# PCB_LED_CALENDAR__SINGLE_MONTH_31D.net
KiCad netlist of a schematic drawn in Altium Designer
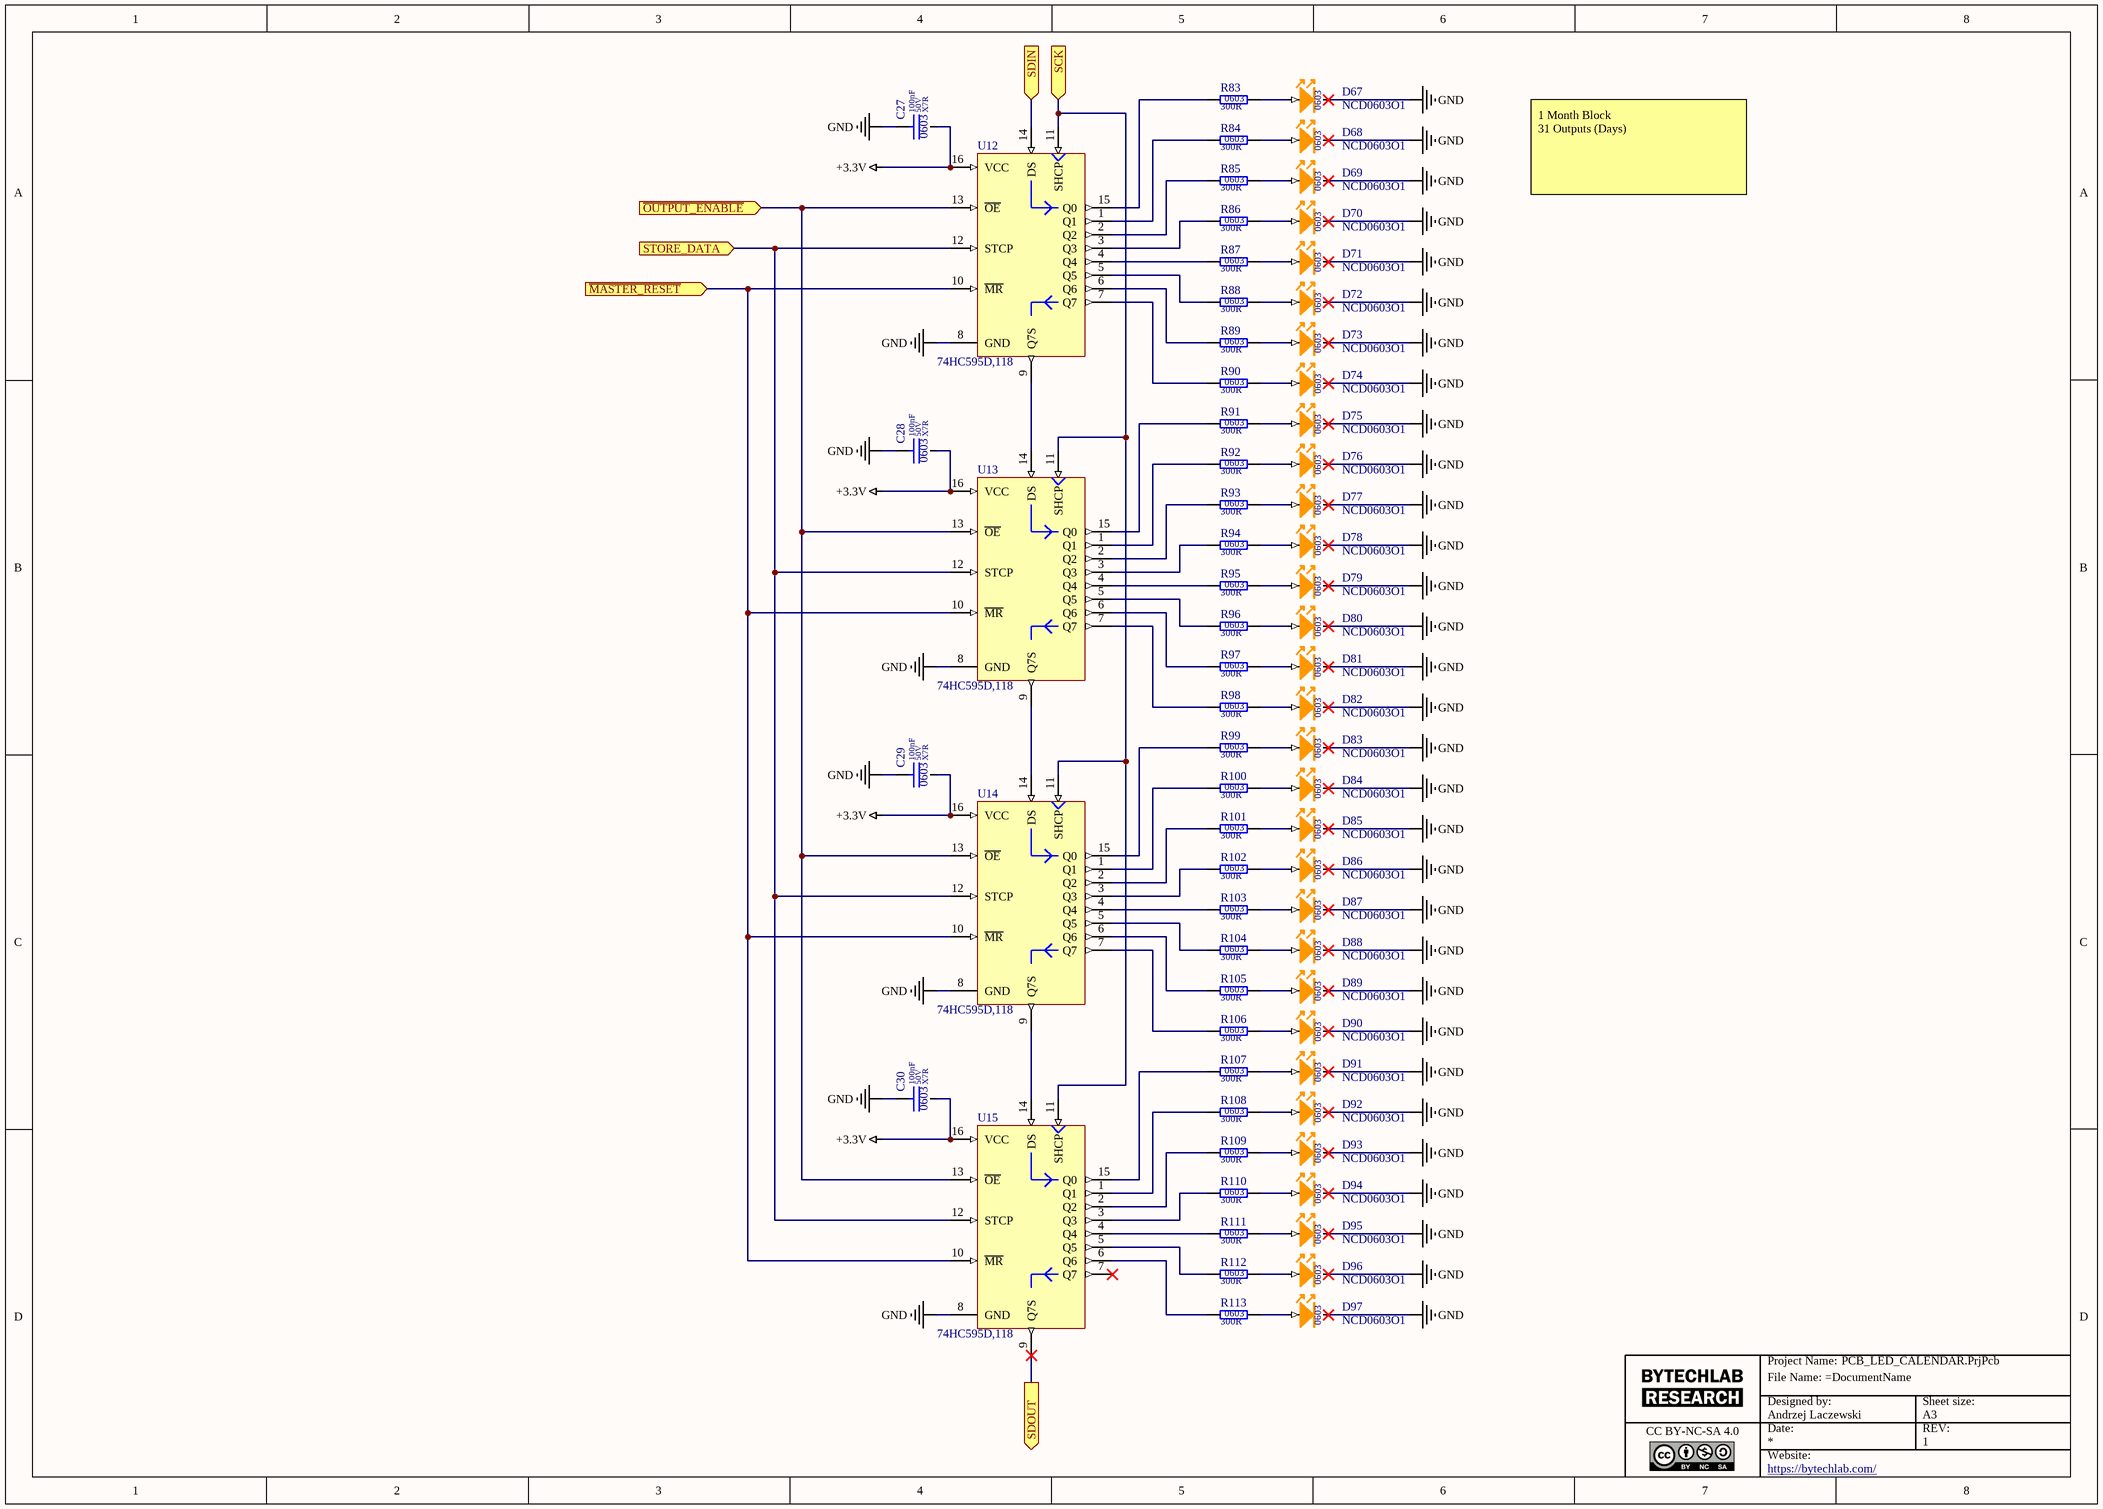
[diagram p0: PCB_LED_CALENDAR__SINGLE_MONTH_31D.SchDoc]

(export (version "E")
  (design (tool "Eeschema 10.0.6"))
  (components
    (comp (ref "C27")
      (value "100nF")
      (footprint "C_0603_1608")
      (description "Capacitor")
      (fields
        (field (name "DIELECTRIC") "X7R")
        (field (name "VOLTAGE") "50V")
        (field (name "SCH_FOOTPRINT") "0603")
        (field (name "PART NUMBER") "C_100nF_50V_X7R_0603_5")
        (field (name "MANUFACTURER") "Samsung")
      )
      (libsource (lib "Library") (part "C"))
    )
    (comp (ref "C28")
      (value "100nF")
      (footprint "C_0603_1608")
      (description "Capacitor")
      (fields
        (field (name "DIELECTRIC") "X7R")
        (field (name "VOLTAGE") "50V")
        (field (name "SCH_FOOTPRINT") "0603")
        (field (name "PART NUMBER") "C_100nF_50V_X7R_0603_5")
        (field (name "MANUFACTURER") "Samsung")
      )
      (libsource (lib "Library") (part "C"))
    )
    (comp (ref "C29")
      (value "100nF")
      (footprint "C_0603_1608")
      (description "Capacitor")
      (fields
        (field (name "DIELECTRIC") "X7R")
        (field (name "VOLTAGE") "50V")
        (field (name "SCH_FOOTPRINT") "0603")
        (field (name "PART NUMBER") "C_100nF_50V_X7R_0603_5")
        (field (name "MANUFACTURER") "Samsung")
      )
      (libsource (lib "Library") (part "C"))
    )
    (comp (ref "C30")
      (value "100nF")
      (footprint "C_0603_1608")
      (description "Capacitor")
      (fields
        (field (name "DIELECTRIC") "X7R")
        (field (name "VOLTAGE") "50V")
        (field (name "SCH_FOOTPRINT") "0603")
        (field (name "PART NUMBER") "C_100nF_50V_X7R_0603_5")
        (field (name "MANUFACTURER") "Samsung")
      )
      (libsource (lib "Library") (part "C"))
    )
    (comp (ref "D67")
      (value "NCD0603O1")
      (footprint "LED_0603")
      (description "Orange 130° 65mW 1.6V~2.6V 0603")
      (fields
        (field (name "MANUFACTURER") "Foshan NationStar Optoelectronics")
        (field (name "SCH_FOOTPRINT") "0603")
      )
      (libsource (lib "PCB_LED_CALENDAR") (part "OL_NCD0603O1"))
    )
    (comp (ref "D68")
      (value "NCD0603O1")
      (footprint "LED_0603")
      (description "Orange 130° 65mW 1.6V~2.6V 0603")
      (fields
        (field (name "MANUFACTURER") "Foshan NationStar Optoelectronics")
        (field (name "SCH_FOOTPRINT") "0603")
      )
      (libsource (lib "PCB_LED_CALENDAR") (part "OL_NCD0603O1"))
    )
    (comp (ref "D69")
      (value "NCD0603O1")
      (footprint "LED_0603")
      (description "Orange 130° 65mW 1.6V~2.6V 0603")
      (fields
        (field (name "MANUFACTURER") "Foshan NationStar Optoelectronics")
        (field (name "SCH_FOOTPRINT") "0603")
      )
      (libsource (lib "PCB_LED_CALENDAR") (part "OL_NCD0603O1"))
    )
    (comp (ref "D70")
      (value "NCD0603O1")
      (footprint "LED_0603")
      (description "Orange 130° 65mW 1.6V~2.6V 0603")
      (fields
        (field (name "MANUFACTURER") "Foshan NationStar Optoelectronics")
        (field (name "SCH_FOOTPRINT") "0603")
      )
      (libsource (lib "PCB_LED_CALENDAR") (part "OL_NCD0603O1"))
    )
    (comp (ref "D71")
      (value "NCD0603O1")
      (footprint "LED_0603")
      (description "Orange 130° 65mW 1.6V~2.6V 0603")
      (fields
        (field (name "MANUFACTURER") "Foshan NationStar Optoelectronics")
        (field (name "SCH_FOOTPRINT") "0603")
      )
      (libsource (lib "PCB_LED_CALENDAR") (part "OL_NCD0603O1"))
    )
    (comp (ref "D72")
      (value "NCD0603O1")
      (footprint "LED_0603")
      (description "Orange 130° 65mW 1.6V~2.6V 0603")
      (fields
        (field (name "MANUFACTURER") "Foshan NationStar Optoelectronics")
        (field (name "SCH_FOOTPRINT") "0603")
      )
      (libsource (lib "PCB_LED_CALENDAR") (part "OL_NCD0603O1"))
    )
    (comp (ref "D73")
      (value "NCD0603O1")
      (footprint "LED_0603")
      (description "Orange 130° 65mW 1.6V~2.6V 0603")
      (fields
        (field (name "MANUFACTURER") "Foshan NationStar Optoelectronics")
        (field (name "SCH_FOOTPRINT") "0603")
      )
      (libsource (lib "PCB_LED_CALENDAR") (part "OL_NCD0603O1"))
    )
    (comp (ref "D74")
      (value "NCD0603O1")
      (footprint "LED_0603")
      (description "Orange 130° 65mW 1.6V~2.6V 0603")
      (fields
        (field (name "MANUFACTURER") "Foshan NationStar Optoelectronics")
        (field (name "SCH_FOOTPRINT") "0603")
      )
      (libsource (lib "PCB_LED_CALENDAR") (part "OL_NCD0603O1"))
    )
    (comp (ref "D75")
      (value "NCD0603O1")
      (footprint "LED_0603")
      (description "Orange 130° 65mW 1.6V~2.6V 0603")
      (fields
        (field (name "MANUFACTURER") "Foshan NationStar Optoelectronics")
        (field (name "SCH_FOOTPRINT") "0603")
      )
      (libsource (lib "PCB_LED_CALENDAR") (part "OL_NCD0603O1"))
    )
    (comp (ref "D76")
      (value "NCD0603O1")
      (footprint "LED_0603")
      (description "Orange 130° 65mW 1.6V~2.6V 0603")
      (fields
        (field (name "MANUFACTURER") "Foshan NationStar Optoelectronics")
        (field (name "SCH_FOOTPRINT") "0603")
      )
      (libsource (lib "PCB_LED_CALENDAR") (part "OL_NCD0603O1"))
    )
    (comp (ref "D77")
      (value "NCD0603O1")
      (footprint "LED_0603")
      (description "Orange 130° 65mW 1.6V~2.6V 0603")
      (fields
        (field (name "MANUFACTURER") "Foshan NationStar Optoelectronics")
        (field (name "SCH_FOOTPRINT") "0603")
      )
      (libsource (lib "PCB_LED_CALENDAR") (part "OL_NCD0603O1"))
    )
    (comp (ref "D78")
      (value "NCD0603O1")
      (footprint "LED_0603")
      (description "Orange 130° 65mW 1.6V~2.6V 0603")
      (fields
        (field (name "MANUFACTURER") "Foshan NationStar Optoelectronics")
        (field (name "SCH_FOOTPRINT") "0603")
      )
      (libsource (lib "PCB_LED_CALENDAR") (part "OL_NCD0603O1"))
    )
    (comp (ref "D79")
      (value "NCD0603O1")
      (footprint "LED_0603")
      (description "Orange 130° 65mW 1.6V~2.6V 0603")
      (fields
        (field (name "MANUFACTURER") "Foshan NationStar Optoelectronics")
        (field (name "SCH_FOOTPRINT") "0603")
      )
      (libsource (lib "PCB_LED_CALENDAR") (part "OL_NCD0603O1"))
    )
    (comp (ref "D80")
      (value "NCD0603O1")
      (footprint "LED_0603")
      (description "Orange 130° 65mW 1.6V~2.6V 0603")
      (fields
        (field (name "MANUFACTURER") "Foshan NationStar Optoelectronics")
        (field (name "SCH_FOOTPRINT") "0603")
      )
      (libsource (lib "PCB_LED_CALENDAR") (part "OL_NCD0603O1"))
    )
    (comp (ref "D81")
      (value "NCD0603O1")
      (footprint "LED_0603")
      (description "Orange 130° 65mW 1.6V~2.6V 0603")
      (fields
        (field (name "MANUFACTURER") "Foshan NationStar Optoelectronics")
        (field (name "SCH_FOOTPRINT") "0603")
      )
      (libsource (lib "PCB_LED_CALENDAR") (part "OL_NCD0603O1"))
    )
    (comp (ref "D82")
      (value "NCD0603O1")
      (footprint "LED_0603")
      (description "Orange 130° 65mW 1.6V~2.6V 0603")
      (fields
        (field (name "MANUFACTURER") "Foshan NationStar Optoelectronics")
        (field (name "SCH_FOOTPRINT") "0603")
      )
      (libsource (lib "PCB_LED_CALENDAR") (part "OL_NCD0603O1"))
    )
    (comp (ref "D83")
      (value "NCD0603O1")
      (footprint "LED_0603")
      (description "Orange 130° 65mW 1.6V~2.6V 0603")
      (fields
        (field (name "MANUFACTURER") "Foshan NationStar Optoelectronics")
        (field (name "SCH_FOOTPRINT") "0603")
      )
      (libsource (lib "PCB_LED_CALENDAR") (part "OL_NCD0603O1"))
    )
    (comp (ref "D84")
      (value "NCD0603O1")
      (footprint "LED_0603")
      (description "Orange 130° 65mW 1.6V~2.6V 0603")
      (fields
        (field (name "MANUFACTURER") "Foshan NationStar Optoelectronics")
        (field (name "SCH_FOOTPRINT") "0603")
      )
      (libsource (lib "PCB_LED_CALENDAR") (part "OL_NCD0603O1"))
    )
    (comp (ref "D85")
      (value "NCD0603O1")
      (footprint "LED_0603")
      (description "Orange 130° 65mW 1.6V~2.6V 0603")
      (fields
        (field (name "MANUFACTURER") "Foshan NationStar Optoelectronics")
        (field (name "SCH_FOOTPRINT") "0603")
      )
      (libsource (lib "PCB_LED_CALENDAR") (part "OL_NCD0603O1"))
    )
    (comp (ref "D86")
      (value "NCD0603O1")
      (footprint "LED_0603")
      (description "Orange 130° 65mW 1.6V~2.6V 0603")
      (fields
        (field (name "MANUFACTURER") "Foshan NationStar Optoelectronics")
        (field (name "SCH_FOOTPRINT") "0603")
      )
      (libsource (lib "PCB_LED_CALENDAR") (part "OL_NCD0603O1"))
    )
    (comp (ref "D87")
      (value "NCD0603O1")
      (footprint "LED_0603")
      (description "Orange 130° 65mW 1.6V~2.6V 0603")
      (fields
        (field (name "MANUFACTURER") "Foshan NationStar Optoelectronics")
        (field (name "SCH_FOOTPRINT") "0603")
      )
      (libsource (lib "PCB_LED_CALENDAR") (part "OL_NCD0603O1"))
    )
    (comp (ref "D88")
      (value "NCD0603O1")
      (footprint "LED_0603")
      (description "Orange 130° 65mW 1.6V~2.6V 0603")
      (fields
        (field (name "MANUFACTURER") "Foshan NationStar Optoelectronics")
        (field (name "SCH_FOOTPRINT") "0603")
      )
      (libsource (lib "PCB_LED_CALENDAR") (part "OL_NCD0603O1"))
    )
    (comp (ref "D89")
      (value "NCD0603O1")
      (footprint "LED_0603")
      (description "Orange 130° 65mW 1.6V~2.6V 0603")
      (fields
        (field (name "MANUFACTURER") "Foshan NationStar Optoelectronics")
        (field (name "SCH_FOOTPRINT") "0603")
      )
      (libsource (lib "PCB_LED_CALENDAR") (part "OL_NCD0603O1"))
    )
    (comp (ref "D90")
      (value "NCD0603O1")
      (footprint "LED_0603")
      (description "Orange 130° 65mW 1.6V~2.6V 0603")
      (fields
        (field (name "MANUFACTURER") "Foshan NationStar Optoelectronics")
        (field (name "SCH_FOOTPRINT") "0603")
      )
      (libsource (lib "PCB_LED_CALENDAR") (part "OL_NCD0603O1"))
    )
    (comp (ref "D91")
      (value "NCD0603O1")
      (footprint "LED_0603")
      (description "Orange 130° 65mW 1.6V~2.6V 0603")
      (fields
        (field (name "MANUFACTURER") "Foshan NationStar Optoelectronics")
        (field (name "SCH_FOOTPRINT") "0603")
      )
      (libsource (lib "PCB_LED_CALENDAR") (part "OL_NCD0603O1"))
    )
    (comp (ref "D92")
      (value "NCD0603O1")
      (footprint "LED_0603")
      (description "Orange 130° 65mW 1.6V~2.6V 0603")
      (fields
        (field (name "MANUFACTURER") "Foshan NationStar Optoelectronics")
        (field (name "SCH_FOOTPRINT") "0603")
      )
      (libsource (lib "PCB_LED_CALENDAR") (part "OL_NCD0603O1"))
    )
    (comp (ref "D93")
      (value "NCD0603O1")
      (footprint "LED_0603")
      (description "Orange 130° 65mW 1.6V~2.6V 0603")
      (fields
        (field (name "MANUFACTURER") "Foshan NationStar Optoelectronics")
        (field (name "SCH_FOOTPRINT") "0603")
      )
      (libsource (lib "PCB_LED_CALENDAR") (part "OL_NCD0603O1"))
    )
    (comp (ref "D94")
      (value "NCD0603O1")
      (footprint "LED_0603")
      (description "Orange 130° 65mW 1.6V~2.6V 0603")
      (fields
        (field (name "MANUFACTURER") "Foshan NationStar Optoelectronics")
        (field (name "SCH_FOOTPRINT") "0603")
      )
      (libsource (lib "PCB_LED_CALENDAR") (part "OL_NCD0603O1"))
    )
    (comp (ref "D95")
      (value "NCD0603O1")
      (footprint "LED_0603")
      (description "Orange 130° 65mW 1.6V~2.6V 0603")
      (fields
        (field (name "MANUFACTURER") "Foshan NationStar Optoelectronics")
        (field (name "SCH_FOOTPRINT") "0603")
      )
      (libsource (lib "PCB_LED_CALENDAR") (part "OL_NCD0603O1"))
    )
    (comp (ref "D96")
      (value "NCD0603O1")
      (footprint "LED_0603")
      (description "Orange 130° 65mW 1.6V~2.6V 0603")
      (fields
        (field (name "MANUFACTURER") "Foshan NationStar Optoelectronics")
        (field (name "SCH_FOOTPRINT") "0603")
      )
      (libsource (lib "PCB_LED_CALENDAR") (part "OL_NCD0603O1"))
    )
    (comp (ref "D97")
      (value "NCD0603O1")
      (footprint "LED_0603")
      (description "Orange 130° 65mW 1.6V~2.6V 0603")
      (fields
        (field (name "MANUFACTURER") "Foshan NationStar Optoelectronics")
        (field (name "SCH_FOOTPRINT") "0603")
      )
      (libsource (lib "PCB_LED_CALENDAR") (part "OL_NCD0603O1"))
    )
    (comp (ref "R83")
      (value "300R")
      (footprint "R_0603_1608")
      (fields
        (field (name "SCH_FOOTPRINT") "0603")
        (field (name "PART NUMBER") "R_300R_0603_1")
        (field (name "VOLTAGE") "50V")
        (field (name "POWER") "100mW")
      )
      (libsource (lib "Library") (part "R"))
    )
    (comp (ref "R84")
      (value "300R")
      (footprint "R_0603_1608")
      (fields
        (field (name "SCH_FOOTPRINT") "0603")
        (field (name "PART NUMBER") "R_300R_0603_1")
        (field (name "VOLTAGE") "50V")
        (field (name "POWER") "100mW")
      )
      (libsource (lib "Library") (part "R"))
    )
    (comp (ref "R85")
      (value "300R")
      (footprint "R_0603_1608")
      (fields
        (field (name "SCH_FOOTPRINT") "0603")
        (field (name "PART NUMBER") "R_300R_0603_1")
        (field (name "VOLTAGE") "50V")
        (field (name "POWER") "100mW")
      )
      (libsource (lib "Library") (part "R"))
    )
    (comp (ref "R86")
      (value "300R")
      (footprint "R_0603_1608")
      (fields
        (field (name "SCH_FOOTPRINT") "0603")
        (field (name "PART NUMBER") "R_300R_0603_1")
        (field (name "VOLTAGE") "50V")
        (field (name "POWER") "100mW")
      )
      (libsource (lib "Library") (part "R"))
    )
    (comp (ref "R87")
      (value "300R")
      (footprint "R_0603_1608")
      (fields
        (field (name "SCH_FOOTPRINT") "0603")
        (field (name "PART NUMBER") "R_300R_0603_1")
        (field (name "VOLTAGE") "50V")
        (field (name "POWER") "100mW")
      )
      (libsource (lib "Library") (part "R"))
    )
    (comp (ref "R88")
      (value "300R")
      (footprint "R_0603_1608")
      (fields
        (field (name "SCH_FOOTPRINT") "0603")
        (field (name "PART NUMBER") "R_300R_0603_1")
        (field (name "VOLTAGE") "50V")
        (field (name "POWER") "100mW")
      )
      (libsource (lib "Library") (part "R"))
    )
    (comp (ref "R89")
      (value "300R")
      (footprint "R_0603_1608")
      (fields
        (field (name "SCH_FOOTPRINT") "0603")
        (field (name "PART NUMBER") "R_300R_0603_1")
        (field (name "VOLTAGE") "50V")
        (field (name "POWER") "100mW")
      )
      (libsource (lib "Library") (part "R"))
    )
    (comp (ref "R90")
      (value "300R")
      (footprint "R_0603_1608")
      (fields
        (field (name "SCH_FOOTPRINT") "0603")
        (field (name "PART NUMBER") "R_300R_0603_1")
        (field (name "VOLTAGE") "50V")
        (field (name "POWER") "100mW")
      )
      (libsource (lib "Library") (part "R"))
    )
    (comp (ref "R91")
      (value "300R")
      (footprint "R_0603_1608")
      (fields
        (field (name "SCH_FOOTPRINT") "0603")
        (field (name "PART NUMBER") "R_300R_0603_1")
        (field (name "VOLTAGE") "50V")
        (field (name "POWER") "100mW")
      )
      (libsource (lib "Library") (part "R"))
    )
    (comp (ref "R92")
      (value "300R")
      (footprint "R_0603_1608")
      (fields
        (field (name "SCH_FOOTPRINT") "0603")
        (field (name "PART NUMBER") "R_300R_0603_1")
        (field (name "VOLTAGE") "50V")
        (field (name "POWER") "100mW")
      )
      (libsource (lib "Library") (part "R"))
    )
    (comp (ref "R93")
      (value "300R")
      (footprint "R_0603_1608")
      (fields
        (field (name "SCH_FOOTPRINT") "0603")
        (field (name "PART NUMBER") "R_300R_0603_1")
        (field (name "VOLTAGE") "50V")
        (field (name "POWER") "100mW")
      )
      (libsource (lib "Library") (part "R"))
    )
    (comp (ref "R94")
      (value "300R")
      (footprint "R_0603_1608")
      (fields
        (field (name "SCH_FOOTPRINT") "0603")
        (field (name "PART NUMBER") "R_300R_0603_1")
        (field (name "VOLTAGE") "50V")
        (field (name "POWER") "100mW")
      )
      (libsource (lib "Library") (part "R"))
    )
    (comp (ref "R95")
      (value "300R")
      (footprint "R_0603_1608")
      (fields
        (field (name "SCH_FOOTPRINT") "0603")
        (field (name "PART NUMBER") "R_300R_0603_1")
        (field (name "VOLTAGE") "50V")
        (field (name "POWER") "100mW")
      )
      (libsource (lib "Library") (part "R"))
    )
    (comp (ref "R96")
      (value "300R")
      (footprint "R_0603_1608")
      (fields
        (field (name "SCH_FOOTPRINT") "0603")
        (field (name "PART NUMBER") "R_300R_0603_1")
        (field (name "VOLTAGE") "50V")
        (field (name "POWER") "100mW")
      )
      (libsource (lib "Library") (part "R"))
    )
    (comp (ref "R97")
      (value "300R")
      (footprint "R_0603_1608")
      (fields
        (field (name "SCH_FOOTPRINT") "0603")
        (field (name "PART NUMBER") "R_300R_0603_1")
        (field (name "VOLTAGE") "50V")
        (field (name "POWER") "100mW")
      )
      (libsource (lib "Library") (part "R"))
    )
    (comp (ref "R98")
      (value "300R")
      (footprint "R_0603_1608")
      (fields
        (field (name "SCH_FOOTPRINT") "0603")
        (field (name "PART NUMBER") "R_300R_0603_1")
        (field (name "VOLTAGE") "50V")
        (field (name "POWER") "100mW")
      )
      (libsource (lib "Library") (part "R"))
    )
    (comp (ref "R99")
      (value "300R")
      (footprint "R_0603_1608")
      (fields
        (field (name "SCH_FOOTPRINT") "0603")
        (field (name "PART NUMBER") "R_300R_0603_1")
        (field (name "VOLTAGE") "50V")
        (field (name "POWER") "100mW")
      )
      (libsource (lib "Library") (part "R"))
    )
    (comp (ref "R100")
      (value "300R")
      (footprint "R_0603_1608")
      (fields
        (field (name "SCH_FOOTPRINT") "0603")
        (field (name "PART NUMBER") "R_300R_0603_1")
        (field (name "VOLTAGE") "50V")
        (field (name "POWER") "100mW")
      )
      (libsource (lib "Library") (part "R"))
    )
    (comp (ref "R101")
      (value "300R")
      (footprint "R_0603_1608")
      (fields
        (field (name "SCH_FOOTPRINT") "0603")
        (field (name "PART NUMBER") "R_300R_0603_1")
        (field (name "VOLTAGE") "50V")
        (field (name "POWER") "100mW")
      )
      (libsource (lib "Library") (part "R"))
    )
    (comp (ref "R102")
      (value "300R")
      (footprint "R_0603_1608")
      (fields
        (field (name "SCH_FOOTPRINT") "0603")
        (field (name "PART NUMBER") "R_300R_0603_1")
        (field (name "VOLTAGE") "50V")
        (field (name "POWER") "100mW")
      )
      (libsource (lib "Library") (part "R"))
    )
    (comp (ref "R103")
      (value "300R")
      (footprint "R_0603_1608")
      (fields
        (field (name "SCH_FOOTPRINT") "0603")
        (field (name "PART NUMBER") "R_300R_0603_1")
        (field (name "VOLTAGE") "50V")
        (field (name "POWER") "100mW")
      )
      (libsource (lib "Library") (part "R"))
    )
    (comp (ref "R104")
      (value "300R")
      (footprint "R_0603_1608")
      (fields
        (field (name "SCH_FOOTPRINT") "0603")
        (field (name "PART NUMBER") "R_300R_0603_1")
        (field (name "VOLTAGE") "50V")
        (field (name "POWER") "100mW")
      )
      (libsource (lib "Library") (part "R"))
    )
    (comp (ref "R105")
      (value "300R")
      (footprint "R_0603_1608")
      (fields
        (field (name "SCH_FOOTPRINT") "0603")
        (field (name "PART NUMBER") "R_300R_0603_1")
        (field (name "VOLTAGE") "50V")
        (field (name "POWER") "100mW")
      )
      (libsource (lib "Library") (part "R"))
    )
    (comp (ref "R106")
      (value "300R")
      (footprint "R_0603_1608")
      (fields
        (field (name "SCH_FOOTPRINT") "0603")
        (field (name "PART NUMBER") "R_300R_0603_1")
        (field (name "VOLTAGE") "50V")
        (field (name "POWER") "100mW")
      )
      (libsource (lib "Library") (part "R"))
    )
    (comp (ref "R107")
      (value "300R")
      (footprint "R_0603_1608")
      (fields
        (field (name "SCH_FOOTPRINT") "0603")
        (field (name "PART NUMBER") "R_300R_0603_1")
        (field (name "VOLTAGE") "50V")
        (field (name "POWER") "100mW")
      )
      (libsource (lib "Library") (part "R"))
    )
    (comp (ref "R108")
      (value "300R")
      (footprint "R_0603_1608")
      (fields
        (field (name "SCH_FOOTPRINT") "0603")
        (field (name "PART NUMBER") "R_300R_0603_1")
        (field (name "VOLTAGE") "50V")
        (field (name "POWER") "100mW")
      )
      (libsource (lib "Library") (part "R"))
    )
    (comp (ref "R109")
      (value "300R")
      (footprint "R_0603_1608")
      (fields
        (field (name "SCH_FOOTPRINT") "0603")
        (field (name "PART NUMBER") "R_300R_0603_1")
        (field (name "VOLTAGE") "50V")
        (field (name "POWER") "100mW")
      )
      (libsource (lib "Library") (part "R"))
    )
    (comp (ref "R110")
      (value "300R")
      (footprint "R_0603_1608")
      (fields
        (field (name "SCH_FOOTPRINT") "0603")
        (field (name "PART NUMBER") "R_300R_0603_1")
        (field (name "VOLTAGE") "50V")
        (field (name "POWER") "100mW")
      )
      (libsource (lib "Library") (part "R"))
    )
    (comp (ref "R111")
      (value "300R")
      (footprint "R_0603_1608")
      (fields
        (field (name "SCH_FOOTPRINT") "0603")
        (field (name "PART NUMBER") "R_300R_0603_1")
        (field (name "VOLTAGE") "50V")
        (field (name "POWER") "100mW")
      )
      (libsource (lib "Library") (part "R"))
    )
    (comp (ref "R112")
      (value "300R")
      (footprint "R_0603_1608")
      (fields
        (field (name "SCH_FOOTPRINT") "0603")
        (field (name "PART NUMBER") "R_300R_0603_1")
        (field (name "VOLTAGE") "50V")
        (field (name "POWER") "100mW")
      )
      (libsource (lib "Library") (part "R"))
    )
    (comp (ref "R113")
      (value "300R")
      (footprint "R_0603_1608")
      (fields
        (field (name "SCH_FOOTPRINT") "0603")
        (field (name "PART NUMBER") "R_300R_0603_1")
        (field (name "VOLTAGE") "50V")
        (field (name "POWER") "100mW")
      )
      (libsource (lib "Library") (part "R"))
    )
    (comp (ref "U12")
      (value "74HC595D,118")
      (footprint "SO16")
      (description "8-bit serial-in, serial or parallel-out shift register with output latches; 3-state")
      (fields (field (name "MANUFACTURER") "Nexperia"))
      (libsource (lib "PCB_LED_CALENDAR") (part "U_74HC595D,118"))
    )
    (comp (ref "U13")
      (value "74HC595D,118")
      (footprint "SO16")
      (description "8-bit serial-in, serial or parallel-out shift register with output latches; 3-state")
      (fields (field (name "MANUFACTURER") "Nexperia"))
      (libsource (lib "PCB_LED_CALENDAR") (part "U_74HC595D,118"))
    )
    (comp (ref "U14")
      (value "74HC595D,118")
      (footprint "SO16")
      (description "8-bit serial-in, serial or parallel-out shift register with output latches; 3-state")
      (fields (field (name "MANUFACTURER") "Nexperia"))
      (libsource (lib "PCB_LED_CALENDAR") (part "U_74HC595D,118"))
    )
    (comp (ref "U15")
      (value "74HC595D,118")
      (footprint "SO16")
      (description "8-bit serial-in, serial or parallel-out shift register with output latches; 3-state")
      (fields (field (name "MANUFACTURER") "Nexperia"))
      (libsource (lib "PCB_LED_CALENDAR") (part "U_74HC595D,118"))
    )
  )
  (nets
    (net (code "1") (name "+3.3V") (class "Default")
      (node (ref "C27") (pin "2") (pinfunction "2_2") (pintype "passive"))
      (node (ref "C28") (pin "2") (pinfunction "2_2") (pintype "passive"))
      (node (ref "C29") (pin "2") (pinfunction "2_2") (pintype "passive"))
      (node (ref "C30") (pin "2") (pinfunction "2_2") (pintype "passive"))
      (node (ref "U12") (pin "16") (pinfunction "VCC_16") (pintype "input"))
      (node (ref "U13") (pin "16") (pinfunction "VCC_16") (pintype "input"))
      (node (ref "U14") (pin "16") (pinfunction "VCC_16") (pintype "input"))
      (node (ref "U15") (pin "16") (pinfunction "VCC_16") (pintype "input"))
    )
    (net (code "2") (name "/SCK") (class "Default")
      (node (ref "U12") (pin "11") (pinfunction "SHCP_11") (pintype "input"))
      (node (ref "U13") (pin "11") (pinfunction "SHCP_11") (pintype "input"))
      (node (ref "U14") (pin "11") (pinfunction "SHCP_11") (pintype "input"))
      (node (ref "U15") (pin "11") (pinfunction "SHCP_11") (pintype "input"))
    )
    (net (code "3") (name "/SDIN") (class "Default")
      (node (ref "U12") (pin "14") (pinfunction "DS_14") (pintype "input"))
    )
    (net (code "4") (name "/SDOUT") (class "Default")
      (node (ref "U15") (pin "9") (pinfunction "Q7S_9") (pintype "output+no_connect"))
    )
    (net (code "5") (name "/STORE_DATA") (class "Default")
      (node (ref "U12") (pin "12") (pinfunction "STCP_12") (pintype "input"))
      (node (ref "U13") (pin "12") (pinfunction "STCP_12") (pintype "input"))
      (node (ref "U14") (pin "12") (pinfunction "STCP_12") (pintype "input"))
      (node (ref "U15") (pin "12") (pinfunction "STCP_12") (pintype "input"))
    )
    (net (code "6") (name "/~{MASTER_RESET}") (class "Default")
      (node (ref "U12") (pin "10") (pinfunction "~{MR}_10") (pintype "input"))
      (node (ref "U13") (pin "10") (pinfunction "~{MR}_10") (pintype "input"))
      (node (ref "U14") (pin "10") (pinfunction "~{MR}_10") (pintype "input"))
      (node (ref "U15") (pin "10") (pinfunction "~{MR}_10") (pintype "input"))
    )
    (net (code "7") (name "/~{OUTPUT_ENABLE}") (class "Default")
      (node (ref "U12") (pin "13") (pinfunction "~{OE}_13") (pintype "input"))
      (node (ref "U13") (pin "13") (pinfunction "~{OE}_13") (pintype "input"))
      (node (ref "U14") (pin "13") (pinfunction "~{OE}_13") (pintype "input"))
      (node (ref "U15") (pin "13") (pinfunction "~{OE}_13") (pintype "input"))
    )
    (net (code "8") (name "GND") (class "Default")
      (node (ref "C27") (pin "1") (pinfunction "1_1") (pintype "passive"))
      (node (ref "C28") (pin "1") (pinfunction "1_1") (pintype "passive"))
      (node (ref "C29") (pin "1") (pinfunction "1_1") (pintype "passive"))
      (node (ref "C30") (pin "1") (pinfunction "1_1") (pintype "passive"))
      (node (ref "D67") (pin "1") (pinfunction "K_1") (pintype "output"))
      (node (ref "D68") (pin "1") (pinfunction "K_1") (pintype "output"))
      (node (ref "D69") (pin "1") (pinfunction "K_1") (pintype "output"))
      (node (ref "D70") (pin "1") (pinfunction "K_1") (pintype "output"))
      (node (ref "D71") (pin "1") (pinfunction "K_1") (pintype "output"))
      (node (ref "D72") (pin "1") (pinfunction "K_1") (pintype "output"))
      (node (ref "D73") (pin "1") (pinfunction "K_1") (pintype "output"))
      (node (ref "D74") (pin "1") (pinfunction "K_1") (pintype "output"))
      (node (ref "D75") (pin "1") (pinfunction "K_1") (pintype "output"))
      (node (ref "D76") (pin "1") (pinfunction "K_1") (pintype "output"))
      (node (ref "D77") (pin "1") (pinfunction "K_1") (pintype "output"))
      (node (ref "D78") (pin "1") (pinfunction "K_1") (pintype "output"))
      (node (ref "D79") (pin "1") (pinfunction "K_1") (pintype "output"))
      (node (ref "D80") (pin "1") (pinfunction "K_1") (pintype "output"))
      (node (ref "D81") (pin "1") (pinfunction "K_1") (pintype "output"))
      (node (ref "D82") (pin "1") (pinfunction "K_1") (pintype "output"))
      (node (ref "D83") (pin "1") (pinfunction "K_1") (pintype "output"))
      (node (ref "D84") (pin "1") (pinfunction "K_1") (pintype "output"))
      (node (ref "D85") (pin "1") (pinfunction "K_1") (pintype "output"))
      (node (ref "D86") (pin "1") (pinfunction "K_1") (pintype "output"))
      (node (ref "D87") (pin "1") (pinfunction "K_1") (pintype "output"))
      (node (ref "D88") (pin "1") (pinfunction "K_1") (pintype "output"))
      (node (ref "D89") (pin "1") (pinfunction "K_1") (pintype "output"))
      (node (ref "D90") (pin "1") (pinfunction "K_1") (pintype "output"))
      (node (ref "D91") (pin "1") (pinfunction "K_1") (pintype "output"))
      (node (ref "D92") (pin "1") (pinfunction "K_1") (pintype "output"))
      (node (ref "D93") (pin "1") (pinfunction "K_1") (pintype "output"))
      (node (ref "D94") (pin "1") (pinfunction "K_1") (pintype "output"))
      (node (ref "D95") (pin "1") (pinfunction "K_1") (pintype "output"))
      (node (ref "D96") (pin "1") (pinfunction "K_1") (pintype "output"))
      (node (ref "D97") (pin "1") (pinfunction "K_1") (pintype "output"))
      (node (ref "U12") (pin "8") (pinfunction "GND_8") (pintype "power_in"))
      (node (ref "U13") (pin "8") (pinfunction "GND_8") (pintype "power_in"))
      (node (ref "U14") (pin "8") (pinfunction "GND_8") (pintype "power_in"))
      (node (ref "U15") (pin "8") (pinfunction "GND_8") (pintype "power_in"))
    )
    (net (code "9") (name "Net-(D67-A)") (class "Default")
      (node (ref "D67") (pin "2") (pinfunction "A_2") (pintype "input"))
      (node (ref "R83") (pin "2") (pinfunction "2_2") (pintype "passive"))
    )
    (net (code "10") (name "Net-(D68-A)") (class "Default")
      (node (ref "D68") (pin "2") (pinfunction "A_2") (pintype "input"))
      (node (ref "R84") (pin "2") (pinfunction "2_2") (pintype "passive"))
    )
    (net (code "11") (name "Net-(D69-A)") (class "Default")
      (node (ref "D69") (pin "2") (pinfunction "A_2") (pintype "input"))
      (node (ref "R85") (pin "2") (pinfunction "2_2") (pintype "passive"))
    )
    (net (code "12") (name "Net-(D70-A)") (class "Default")
      (node (ref "D70") (pin "2") (pinfunction "A_2") (pintype "input"))
      (node (ref "R86") (pin "2") (pinfunction "2_2") (pintype "passive"))
    )
    (net (code "13") (name "Net-(D71-A)") (class "Default")
      (node (ref "D71") (pin "2") (pinfunction "A_2") (pintype "input"))
      (node (ref "R87") (pin "2") (pinfunction "2_2") (pintype "passive"))
    )
    (net (code "14") (name "Net-(D72-A)") (class "Default")
      (node (ref "D72") (pin "2") (pinfunction "A_2") (pintype "input"))
      (node (ref "R88") (pin "2") (pinfunction "2_2") (pintype "passive"))
    )
    (net (code "15") (name "Net-(D73-A)") (class "Default")
      (node (ref "D73") (pin "2") (pinfunction "A_2") (pintype "input"))
      (node (ref "R89") (pin "2") (pinfunction "2_2") (pintype "passive"))
    )
    (net (code "16") (name "Net-(D74-A)") (class "Default")
      (node (ref "D74") (pin "2") (pinfunction "A_2") (pintype "input"))
      (node (ref "R90") (pin "2") (pinfunction "2_2") (pintype "passive"))
    )
    (net (code "17") (name "Net-(D75-A)") (class "Default")
      (node (ref "D75") (pin "2") (pinfunction "A_2") (pintype "input"))
      (node (ref "R91") (pin "2") (pinfunction "2_2") (pintype "passive"))
    )
    (net (code "18") (name "Net-(D76-A)") (class "Default")
      (node (ref "D76") (pin "2") (pinfunction "A_2") (pintype "input"))
      (node (ref "R92") (pin "2") (pinfunction "2_2") (pintype "passive"))
    )
    (net (code "19") (name "Net-(D77-A)") (class "Default")
      (node (ref "D77") (pin "2") (pinfunction "A_2") (pintype "input"))
      (node (ref "R93") (pin "2") (pinfunction "2_2") (pintype "passive"))
    )
    (net (code "20") (name "Net-(D78-A)") (class "Default")
      (node (ref "D78") (pin "2") (pinfunction "A_2") (pintype "input"))
      (node (ref "R94") (pin "2") (pinfunction "2_2") (pintype "passive"))
    )
    (net (code "21") (name "Net-(D79-A)") (class "Default")
      (node (ref "D79") (pin "2") (pinfunction "A_2") (pintype "input"))
      (node (ref "R95") (pin "2") (pinfunction "2_2") (pintype "passive"))
    )
    (net (code "22") (name "Net-(D80-A)") (class "Default")
      (node (ref "D80") (pin "2") (pinfunction "A_2") (pintype "input"))
      (node (ref "R96") (pin "2") (pinfunction "2_2") (pintype "passive"))
    )
    (net (code "23") (name "Net-(D81-A)") (class "Default")
      (node (ref "D81") (pin "2") (pinfunction "A_2") (pintype "input"))
      (node (ref "R97") (pin "2") (pinfunction "2_2") (pintype "passive"))
    )
    (net (code "24") (name "Net-(D82-A)") (class "Default")
      (node (ref "D82") (pin "2") (pinfunction "A_2") (pintype "input"))
      (node (ref "R98") (pin "2") (pinfunction "2_2") (pintype "passive"))
    )
    (net (code "25") (name "Net-(D83-A)") (class "Default")
      (node (ref "D83") (pin "2") (pinfunction "A_2") (pintype "input"))
      (node (ref "R99") (pin "2") (pinfunction "2_2") (pintype "passive"))
    )
    (net (code "26") (name "Net-(D84-A)") (class "Default")
      (node (ref "D84") (pin "2") (pinfunction "A_2") (pintype "input"))
      (node (ref "R100") (pin "2") (pinfunction "2_2") (pintype "passive"))
    )
    (net (code "27") (name "Net-(D85-A)") (class "Default")
      (node (ref "D85") (pin "2") (pinfunction "A_2") (pintype "input"))
      (node (ref "R101") (pin "2") (pinfunction "2_2") (pintype "passive"))
    )
    (net (code "28") (name "Net-(D86-A)") (class "Default")
      (node (ref "D86") (pin "2") (pinfunction "A_2") (pintype "input"))
      (node (ref "R102") (pin "2") (pinfunction "2_2") (pintype "passive"))
    )
    (net (code "29") (name "Net-(D87-A)") (class "Default")
      (node (ref "D87") (pin "2") (pinfunction "A_2") (pintype "input"))
      (node (ref "R103") (pin "2") (pinfunction "2_2") (pintype "passive"))
    )
    (net (code "30") (name "Net-(D88-A)") (class "Default")
      (node (ref "D88") (pin "2") (pinfunction "A_2") (pintype "input"))
      (node (ref "R104") (pin "2") (pinfunction "2_2") (pintype "passive"))
    )
    (net (code "31") (name "Net-(D89-A)") (class "Default")
      (node (ref "D89") (pin "2") (pinfunction "A_2") (pintype "input"))
      (node (ref "R105") (pin "2") (pinfunction "2_2") (pintype "passive"))
    )
    (net (code "32") (name "Net-(D90-A)") (class "Default")
      (node (ref "D90") (pin "2") (pinfunction "A_2") (pintype "input"))
      (node (ref "R106") (pin "2") (pinfunction "2_2") (pintype "passive"))
    )
    (net (code "33") (name "Net-(D91-A)") (class "Default")
      (node (ref "D91") (pin "2") (pinfunction "A_2") (pintype "input"))
      (node (ref "R107") (pin "2") (pinfunction "2_2") (pintype "passive"))
    )
    (net (code "34") (name "Net-(D92-A)") (class "Default")
      (node (ref "D92") (pin "2") (pinfunction "A_2") (pintype "input"))
      (node (ref "R108") (pin "2") (pinfunction "2_2") (pintype "passive"))
    )
    (net (code "35") (name "Net-(D93-A)") (class "Default")
      (node (ref "D93") (pin "2") (pinfunction "A_2") (pintype "input"))
      (node (ref "R109") (pin "2") (pinfunction "2_2") (pintype "passive"))
    )
    (net (code "36") (name "Net-(D94-A)") (class "Default")
      (node (ref "D94") (pin "2") (pinfunction "A_2") (pintype "input"))
      (node (ref "R110") (pin "2") (pinfunction "2_2") (pintype "passive"))
    )
    (net (code "37") (name "Net-(D95-A)") (class "Default")
      (node (ref "D95") (pin "2") (pinfunction "A_2") (pintype "input"))
      (node (ref "R111") (pin "2") (pinfunction "2_2") (pintype "passive"))
    )
    (net (code "38") (name "Net-(D96-A)") (class "Default")
      (node (ref "D96") (pin "2") (pinfunction "A_2") (pintype "input"))
      (node (ref "R112") (pin "2") (pinfunction "2_2") (pintype "passive"))
    )
    (net (code "39") (name "Net-(D97-A)") (class "Default")
      (node (ref "D97") (pin "2") (pinfunction "A_2") (pintype "input"))
      (node (ref "R113") (pin "2") (pinfunction "2_2") (pintype "passive"))
    )
    (net (code "40") (name "Net-(U12-Q0)") (class "Default")
      (node (ref "R83") (pin "1") (pinfunction "1_1") (pintype "passive"))
      (node (ref "U12") (pin "15") (pinfunction "Q0_15") (pintype "output"))
    )
    (net (code "41") (name "Net-(U12-Q1)") (class "Default")
      (node (ref "R84") (pin "1") (pinfunction "1_1") (pintype "passive"))
      (node (ref "U12") (pin "1") (pinfunction "Q1_1") (pintype "output"))
    )
    (net (code "42") (name "Net-(U12-Q2)") (class "Default")
      (node (ref "R85") (pin "1") (pinfunction "1_1") (pintype "passive"))
      (node (ref "U12") (pin "2") (pinfunction "Q2_2") (pintype "output"))
    )
    (net (code "43") (name "Net-(U12-Q3)") (class "Default")
      (node (ref "R86") (pin "1") (pinfunction "1_1") (pintype "passive"))
      (node (ref "U12") (pin "3") (pinfunction "Q3_3") (pintype "output"))
    )
    (net (code "44") (name "Net-(U12-Q4)") (class "Default")
      (node (ref "R87") (pin "1") (pinfunction "1_1") (pintype "passive"))
      (node (ref "U12") (pin "4") (pinfunction "Q4_4") (pintype "output"))
    )
    (net (code "45") (name "Net-(U12-Q5)") (class "Default")
      (node (ref "R88") (pin "1") (pinfunction "1_1") (pintype "passive"))
      (node (ref "U12") (pin "5") (pinfunction "Q5_5") (pintype "output"))
    )
    (net (code "46") (name "Net-(U12-Q6)") (class "Default")
      (node (ref "R89") (pin "1") (pinfunction "1_1") (pintype "passive"))
      (node (ref "U12") (pin "6") (pinfunction "Q6_6") (pintype "output"))
    )
    (net (code "47") (name "Net-(U12-Q7)") (class "Default")
      (node (ref "R90") (pin "1") (pinfunction "1_1") (pintype "passive"))
      (node (ref "U12") (pin "7") (pinfunction "Q7_7") (pintype "output"))
    )
    (net (code "48") (name "Net-(U12-Q7S)") (class "Default")
      (node (ref "U12") (pin "9") (pinfunction "Q7S_9") (pintype "output"))
      (node (ref "U13") (pin "14") (pinfunction "DS_14") (pintype "input"))
    )
    (net (code "49") (name "Net-(U13-Q0)") (class "Default")
      (node (ref "R91") (pin "1") (pinfunction "1_1") (pintype "passive"))
      (node (ref "U13") (pin "15") (pinfunction "Q0_15") (pintype "output"))
    )
    (net (code "50") (name "Net-(U13-Q1)") (class "Default")
      (node (ref "R92") (pin "1") (pinfunction "1_1") (pintype "passive"))
      (node (ref "U13") (pin "1") (pinfunction "Q1_1") (pintype "output"))
    )
    (net (code "51") (name "Net-(U13-Q2)") (class "Default")
      (node (ref "R93") (pin "1") (pinfunction "1_1") (pintype "passive"))
      (node (ref "U13") (pin "2") (pinfunction "Q2_2") (pintype "output"))
    )
    (net (code "52") (name "Net-(U13-Q3)") (class "Default")
      (node (ref "R94") (pin "1") (pinfunction "1_1") (pintype "passive"))
      (node (ref "U13") (pin "3") (pinfunction "Q3_3") (pintype "output"))
    )
    (net (code "53") (name "Net-(U13-Q4)") (class "Default")
      (node (ref "R95") (pin "1") (pinfunction "1_1") (pintype "passive"))
      (node (ref "U13") (pin "4") (pinfunction "Q4_4") (pintype "output"))
    )
    (net (code "54") (name "Net-(U13-Q5)") (class "Default")
      (node (ref "R96") (pin "1") (pinfunction "1_1") (pintype "passive"))
      (node (ref "U13") (pin "5") (pinfunction "Q5_5") (pintype "output"))
    )
    (net (code "55") (name "Net-(U13-Q6)") (class "Default")
      (node (ref "R97") (pin "1") (pinfunction "1_1") (pintype "passive"))
      (node (ref "U13") (pin "6") (pinfunction "Q6_6") (pintype "output"))
    )
    (net (code "56") (name "Net-(U13-Q7)") (class "Default")
      (node (ref "R98") (pin "1") (pinfunction "1_1") (pintype "passive"))
      (node (ref "U13") (pin "7") (pinfunction "Q7_7") (pintype "output"))
    )
    (net (code "57") (name "Net-(U13-Q7S)") (class "Default")
      (node (ref "U13") (pin "9") (pinfunction "Q7S_9") (pintype "output"))
      (node (ref "U14") (pin "14") (pinfunction "DS_14") (pintype "input"))
    )
    (net (code "58") (name "Net-(U14-Q0)") (class "Default")
      (node (ref "R99") (pin "1") (pinfunction "1_1") (pintype "passive"))
      (node (ref "U14") (pin "15") (pinfunction "Q0_15") (pintype "output"))
    )
    (net (code "59") (name "Net-(U14-Q1)") (class "Default")
      (node (ref "R100") (pin "1") (pinfunction "1_1") (pintype "passive"))
      (node (ref "U14") (pin "1") (pinfunction "Q1_1") (pintype "output"))
    )
    (net (code "60") (name "Net-(U14-Q2)") (class "Default")
      (node (ref "R101") (pin "1") (pinfunction "1_1") (pintype "passive"))
      (node (ref "U14") (pin "2") (pinfunction "Q2_2") (pintype "output"))
    )
    (net (code "61") (name "Net-(U14-Q3)") (class "Default")
      (node (ref "R102") (pin "1") (pinfunction "1_1") (pintype "passive"))
      (node (ref "U14") (pin "3") (pinfunction "Q3_3") (pintype "output"))
    )
    (net (code "62") (name "Net-(U14-Q4)") (class "Default")
      (node (ref "R103") (pin "1") (pinfunction "1_1") (pintype "passive"))
      (node (ref "U14") (pin "4") (pinfunction "Q4_4") (pintype "output"))
    )
    (net (code "63") (name "Net-(U14-Q5)") (class "Default")
      (node (ref "R104") (pin "1") (pinfunction "1_1") (pintype "passive"))
      (node (ref "U14") (pin "5") (pinfunction "Q5_5") (pintype "output"))
    )
    (net (code "64") (name "Net-(U14-Q6)") (class "Default")
      (node (ref "R105") (pin "1") (pinfunction "1_1") (pintype "passive"))
      (node (ref "U14") (pin "6") (pinfunction "Q6_6") (pintype "output"))
    )
    (net (code "65") (name "Net-(U14-Q7)") (class "Default")
      (node (ref "R106") (pin "1") (pinfunction "1_1") (pintype "passive"))
      (node (ref "U14") (pin "7") (pinfunction "Q7_7") (pintype "output"))
    )
    (net (code "66") (name "Net-(U14-Q7S)") (class "Default")
      (node (ref "U14") (pin "9") (pinfunction "Q7S_9") (pintype "output"))
      (node (ref "U15") (pin "14") (pinfunction "DS_14") (pintype "input"))
    )
    (net (code "67") (name "Net-(U15-Q0)") (class "Default")
      (node (ref "R107") (pin "1") (pinfunction "1_1") (pintype "passive"))
      (node (ref "U15") (pin "15") (pinfunction "Q0_15") (pintype "output"))
    )
    (net (code "68") (name "Net-(U15-Q1)") (class "Default")
      (node (ref "R108") (pin "1") (pinfunction "1_1") (pintype "passive"))
      (node (ref "U15") (pin "1") (pinfunction "Q1_1") (pintype "output"))
    )
    (net (code "69") (name "Net-(U15-Q2)") (class "Default")
      (node (ref "R109") (pin "1") (pinfunction "1_1") (pintype "passive"))
      (node (ref "U15") (pin "2") (pinfunction "Q2_2") (pintype "output"))
    )
    (net (code "70") (name "Net-(U15-Q3)") (class "Default")
      (node (ref "R110") (pin "1") (pinfunction "1_1") (pintype "passive"))
      (node (ref "U15") (pin "3") (pinfunction "Q3_3") (pintype "output"))
    )
    (net (code "71") (name "Net-(U15-Q4)") (class "Default")
      (node (ref "R111") (pin "1") (pinfunction "1_1") (pintype "passive"))
      (node (ref "U15") (pin "4") (pinfunction "Q4_4") (pintype "output"))
    )
    (net (code "72") (name "Net-(U15-Q5)") (class "Default")
      (node (ref "R112") (pin "1") (pinfunction "1_1") (pintype "passive"))
      (node (ref "U15") (pin "5") (pinfunction "Q5_5") (pintype "output"))
    )
    (net (code "73") (name "Net-(U15-Q6)") (class "Default")
      (node (ref "R113") (pin "1") (pinfunction "1_1") (pintype "passive"))
      (node (ref "U15") (pin "6") (pinfunction "Q6_6") (pintype "output"))
    )
    (net (code "74") (name "unconnected-(U15-Q7-Pad7)") (class "Default")
      (node (ref "U15") (pin "7") (pinfunction "Q7_7") (pintype "output+no_connect"))
    )
  )
)
